# 1-Schematic_GPIO_WAVER.net
KiCad netlist of a schematic drawn in EasyEDA
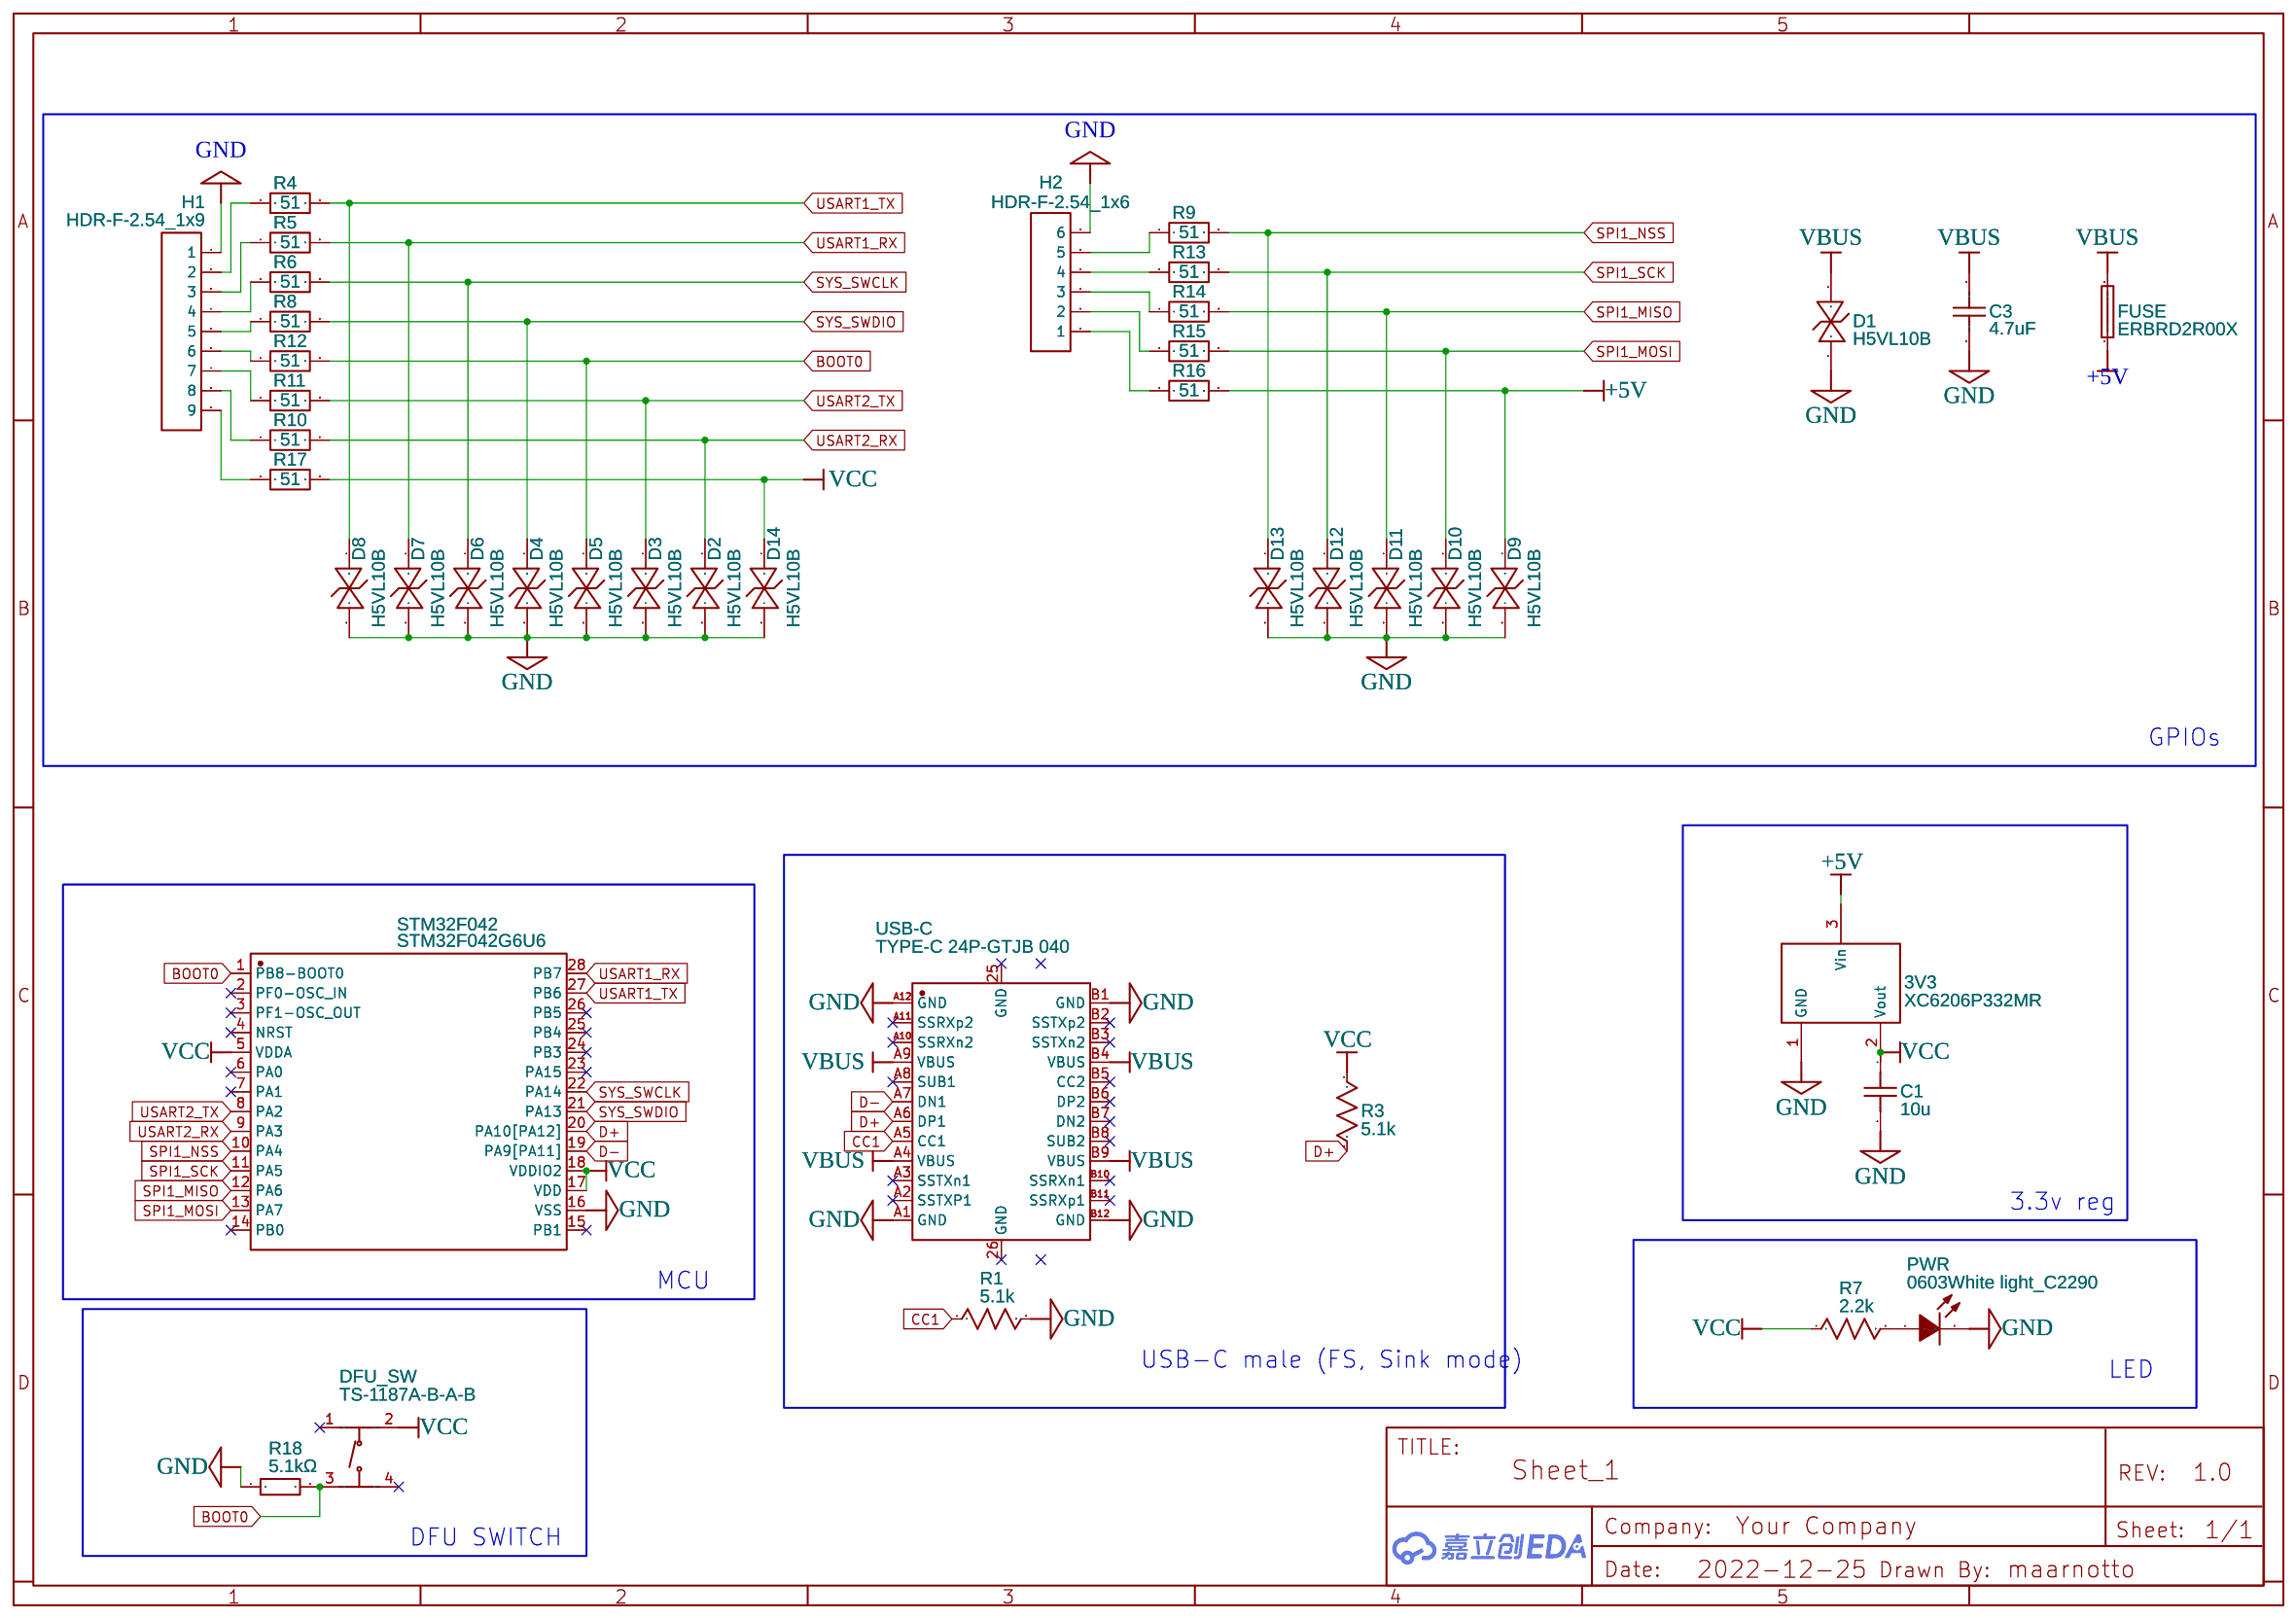
[diagram p0: schematic sheet]

(export (version "E")
  (design (tool "Eeschema 10.0.6"))
  (components
    (comp (ref "3V3")
      (value "XC6206P332MR")
      (fields (field (name "Manufacturer") "TOREX(特瑞仕)"))
      (libsource (lib "") (part "XC6206P332MR"))
    )
    (comp (ref "C1") (value "10u") (libsource (lib "") (part "C_0603_US")))
    (comp (ref "C3") (value "4.7uF") (libsource (lib "") (part "C_0603_US_1")))
    (comp (ref "D1")
      (value "H5VL10B")
      (fields (field (name "Manufacturer") "宏迦橙"))
      (libsource (lib "") (part "H5VL10B"))
    )
    (comp (ref "D2")
      (value "H5VL10B")
      (fields (field (name "Manufacturer") "宏迦橙"))
      (libsource (lib "") (part "H5VL10B"))
    )
    (comp (ref "D3")
      (value "H5VL10B")
      (fields (field (name "Manufacturer") "宏迦橙"))
      (libsource (lib "") (part "H5VL10B"))
    )
    (comp (ref "D4")
      (value "H5VL10B")
      (fields (field (name "Manufacturer") "宏迦橙"))
      (libsource (lib "") (part "H5VL10B"))
    )
    (comp (ref "D5")
      (value "H5VL10B")
      (fields (field (name "Manufacturer") "宏迦橙"))
      (libsource (lib "") (part "H5VL10B"))
    )
    (comp (ref "D6")
      (value "H5VL10B")
      (fields (field (name "Manufacturer") "宏迦橙"))
      (libsource (lib "") (part "H5VL10B"))
    )
    (comp (ref "D7")
      (value "H5VL10B")
      (fields (field (name "Manufacturer") "宏迦橙"))
      (libsource (lib "") (part "H5VL10B"))
    )
    (comp (ref "D8")
      (value "H5VL10B")
      (fields (field (name "Manufacturer") "宏迦橙"))
      (libsource (lib "") (part "H5VL10B"))
    )
    (comp (ref "D9")
      (value "H5VL10B")
      (fields (field (name "Manufacturer") "宏迦橙"))
      (libsource (lib "") (part "H5VL10B"))
    )
    (comp (ref "D10")
      (value "H5VL10B")
      (fields (field (name "Manufacturer") "宏迦橙"))
      (libsource (lib "") (part "H5VL10B"))
    )
    (comp (ref "D11")
      (value "H5VL10B")
      (fields (field (name "Manufacturer") "宏迦橙"))
      (libsource (lib "") (part "H5VL10B"))
    )
    (comp (ref "D12")
      (value "H5VL10B")
      (fields (field (name "Manufacturer") "宏迦橙"))
      (libsource (lib "") (part "H5VL10B"))
    )
    (comp (ref "D13")
      (value "H5VL10B")
      (fields (field (name "Manufacturer") "宏迦橙"))
      (libsource (lib "") (part "H5VL10B"))
    )
    (comp (ref "D14")
      (value "H5VL10B")
      (fields (field (name "Manufacturer") "宏迦橙"))
      (libsource (lib "") (part "H5VL10B"))
    )
    (comp (ref "DFU_SW")
      (value "TS-1187A-B-A-B")
      (fields (field (name "Manufacturer") "XKB Connectivity(中国星坤)"))
      (libsource (lib "") (part "TS-1187A-B-A-B"))
    )
    (comp (ref "FUSE")
      (value "ERBRD2R00X")
      (fields (field (name "Manufacturer") "PANASONIC(松下)"))
      (libsource (lib "") (part "ERBRD2R00X"))
    )
    (comp (ref "H1") (value "HDR-F-2.54_1x9") (libsource (lib "") (part "HDR-F-2.54_1x9")))
    (comp (ref "H2") (value "HDR-F-2.54_1x6") (libsource (lib "") (part "HDR-F-2.54_1x6")))
    (comp (ref "PWR")
      (value "0603White light_C2290")
      (fields (field (name "Manufacturer Part") "KT-0603白灯"))
      (libsource (lib "") (part "0603White light_C2290"))
    )
    (comp (ref "R1") (value "5.1k") (libsource (lib "") (part "R_0603_US")))
    (comp (ref "R3") (value "5.1k") (libsource (lib "") (part "R_0603_US_1")))
    (comp (ref "R4") (value "51") (libsource (lib "") (part "R_0603_EU")))
    (comp (ref "R5") (value "51") (libsource (lib "") (part "R_0603_EU")))
    (comp (ref "R6") (value "51") (libsource (lib "") (part "R_0603_EU")))
    (comp (ref "R7") (value "2.2k") (libsource (lib "") (part "R_0603_US")))
    (comp (ref "R8") (value "51") (libsource (lib "") (part "R_0603_EU")))
    (comp (ref "R9") (value "51") (libsource (lib "") (part "R_0603_EU")))
    (comp (ref "R10") (value "51") (libsource (lib "") (part "R_0603_EU")))
    (comp (ref "R11") (value "51") (libsource (lib "") (part "R_0603_EU")))
    (comp (ref "R12") (value "51") (libsource (lib "") (part "R_0603_EU")))
    (comp (ref "R13") (value "51") (libsource (lib "") (part "R_0603_EU")))
    (comp (ref "R14") (value "51") (libsource (lib "") (part "R_0603_EU")))
    (comp (ref "R15") (value "51") (libsource (lib "") (part "R_0603_EU")))
    (comp (ref "R16") (value "51") (libsource (lib "") (part "R_0603_EU")))
    (comp (ref "R17") (value "51") (libsource (lib "") (part "R_0603_EU")))
    (comp (ref "R18")
      (value "5.1kΩ")
      (fields
        (field (name "Manufacturer Part") "0402WGF5101TCE")
        (field (name "Manufacturer") "UNI-ROYAL(厚声)")
      )
      (libsource (lib "") (part "0402WGF5101TCE"))
    )
    (comp (ref "STM32F042")
      (value "STM32F042G6U6")
      (fields (field (name "Manufacturer") "ST(意法半导体)"))
      (libsource (lib "") (part "STM32F042G6U6"))
    )
    (comp (ref "USB-C")
      (value "TYPE-C 24P-GTJB 040")
      (fields (field (name "Manufacturer") "SHOU HAN(首韩)"))
      (libsource (lib "") (part "TYPE-C 24P-GTJB 040"))
    )
  )
  (nets
    (net (code "1") (name "+5V") (class "Default")
      (node (ref "3V3") (pin "3") (pinfunction "Vin_3") (pintype "unspecified"))
      (node (ref "D9") (pin "1") (pinfunction "C_1") (pintype "unspecified"))
      (node (ref "FUSE") (pin "1") (pinfunction "1_1") (pintype "unspecified"))
      (node (ref "R16") (pin "2") (pinfunction "2_2") (pintype "unspecified"))
    )
    (net (code "2") (name "BOOT0") (class "Default")
      (node (ref "D5") (pin "1") (pinfunction "C_1") (pintype "unspecified"))
      (node (ref "DFU_SW") (pin "3") (pinfunction "C_3") (pintype "unspecified"))
      (node (ref "R12") (pin "2") (pinfunction "2_2") (pintype "unspecified"))
      (node (ref "R18") (pin "2") (pinfunction "2_2") (pintype "input"))
      (node (ref "STM32F042") (pin "1") (pinfunction "PB8-BOOT0_1") (pintype "unspecified"))
    )
    (net (code "3") (name "CC1") (class "Default")
      (node (ref "R1") (pin "1") (pinfunction "1_1") (pintype "unspecified"))
      (node (ref "USB-C") (pin "A5") (pinfunction "CC1_A5") (pintype "unspecified"))
    )
    (net (code "4") (name "D+") (class "Default")
      (node (ref "R3") (pin "2") (pinfunction "2_2") (pintype "unspecified"))
      (node (ref "STM32F042") (pin "20") (pinfunction "PA10[PA12]_20") (pintype "unspecified"))
      (node (ref "USB-C") (pin "A6") (pinfunction "DP1_A6") (pintype "unspecified"))
    )
    (net (code "5") (name "D-") (class "Default")
      (node (ref "STM32F042") (pin "19") (pinfunction "PA9[PA11]_19") (pintype "unspecified"))
      (node (ref "USB-C") (pin "A7") (pinfunction "DN1_A7") (pintype "unspecified"))
    )
    (net (code "6") (name "GND") (class "Default")
      (node (ref "3V3") (pin "1") (pinfunction "GND_1") (pintype "unspecified"))
      (node (ref "C1") (pin "2") (pinfunction "2_2") (pintype "unspecified"))
      (node (ref "C3") (pin "1") (pinfunction "1_1") (pintype "unspecified"))
      (node (ref "D1") (pin "2") (pinfunction "A_2") (pintype "unspecified"))
      (node (ref "D10") (pin "2") (pinfunction "A_2") (pintype "unspecified"))
      (node (ref "D11") (pin "2") (pinfunction "A_2") (pintype "unspecified"))
      (node (ref "D12") (pin "2") (pinfunction "A_2") (pintype "unspecified"))
      (node (ref "D13") (pin "2") (pinfunction "A_2") (pintype "unspecified"))
      (node (ref "D14") (pin "2") (pinfunction "A_2") (pintype "unspecified"))
      (node (ref "D2") (pin "2") (pinfunction "A_2") (pintype "unspecified"))
      (node (ref "D3") (pin "2") (pinfunction "A_2") (pintype "unspecified"))
      (node (ref "D4") (pin "2") (pinfunction "A_2") (pintype "unspecified"))
      (node (ref "D5") (pin "2") (pinfunction "A_2") (pintype "unspecified"))
      (node (ref "D6") (pin "2") (pinfunction "A_2") (pintype "unspecified"))
      (node (ref "D7") (pin "2") (pinfunction "A_2") (pintype "unspecified"))
      (node (ref "D8") (pin "2") (pinfunction "A_2") (pintype "unspecified"))
      (node (ref "D9") (pin "2") (pinfunction "A_2") (pintype "unspecified"))
      (node (ref "H1") (pin "1") (pinfunction "1_1") (pintype "unspecified"))
      (node (ref "H2") (pin "6") (pinfunction "6_6") (pintype "input"))
      (node (ref "PWR") (pin "2") (pinfunction "K_2") (pintype "unspecified"))
      (node (ref "R1") (pin "2") (pinfunction "2_2") (pintype "unspecified"))
      (node (ref "R18") (pin "1") (pinfunction "1_1") (pintype "input"))
      (node (ref "STM32F042") (pin "16") (pinfunction "VSS_16") (pintype "unspecified"))
      (node (ref "USB-C") (pin "A1") (pinfunction "GND_A1") (pintype "unspecified"))
      (node (ref "USB-C") (pin "A12") (pinfunction "GND_A12") (pintype "unspecified"))
      (node (ref "USB-C") (pin "B1") (pinfunction "GND_B1") (pintype "unspecified"))
      (node (ref "USB-C") (pin "B12") (pinfunction "GND_B12") (pintype "unspecified"))
    )
    (net (code "7") (name "Net-(H1-Pad2)") (class "Default")
      (node (ref "H1") (pin "2") (pinfunction "2_2") (pintype "unspecified"))
      (node (ref "R4") (pin "1") (pinfunction "1_1") (pintype "unspecified"))
    )
    (net (code "8") (name "Net-(H1-Pad3)") (class "Default")
      (node (ref "H1") (pin "3") (pinfunction "3_3") (pintype "unspecified"))
      (node (ref "R5") (pin "1") (pinfunction "1_1") (pintype "unspecified"))
    )
    (net (code "9") (name "Net-(H1-Pad4)") (class "Default")
      (node (ref "H1") (pin "4") (pinfunction "4_4") (pintype "unspecified"))
      (node (ref "R6") (pin "1") (pinfunction "1_1") (pintype "unspecified"))
    )
    (net (code "10") (name "Net-(H1-Pad5)") (class "Default")
      (node (ref "H1") (pin "5") (pinfunction "5_5") (pintype "unspecified"))
      (node (ref "R8") (pin "1") (pinfunction "1_1") (pintype "unspecified"))
    )
    (net (code "11") (name "Net-(H1-Pad6)") (class "Default")
      (node (ref "H1") (pin "6") (pinfunction "6_6") (pintype "unspecified"))
      (node (ref "R12") (pin "1") (pinfunction "1_1") (pintype "unspecified"))
    )
    (net (code "12") (name "Net-(H1-Pad7)") (class "Default")
      (node (ref "H1") (pin "7") (pinfunction "7_7") (pintype "unspecified"))
      (node (ref "R11") (pin "1") (pinfunction "1_1") (pintype "unspecified"))
    )
    (net (code "13") (name "Net-(H1-Pad8)") (class "Default")
      (node (ref "H1") (pin "8") (pinfunction "8_8") (pintype "unspecified"))
      (node (ref "R10") (pin "1") (pinfunction "1_1") (pintype "unspecified"))
    )
    (net (code "14") (name "Net-(H1-Pad9)") (class "Default")
      (node (ref "H1") (pin "9") (pinfunction "9_9") (pintype "unspecified"))
      (node (ref "R17") (pin "1") (pinfunction "1_1") (pintype "unspecified"))
    )
    (net (code "15") (name "Net-(H2-Pad1)") (class "Default")
      (node (ref "H2") (pin "1") (pinfunction "1_1") (pintype "input"))
      (node (ref "R16") (pin "1") (pinfunction "1_1") (pintype "unspecified"))
    )
    (net (code "16") (name "Net-(H2-Pad2)") (class "Default")
      (node (ref "H2") (pin "2") (pinfunction "2_2") (pintype "input"))
      (node (ref "R15") (pin "1") (pinfunction "1_1") (pintype "unspecified"))
    )
    (net (code "17") (name "Net-(H2-Pad3)") (class "Default")
      (node (ref "H2") (pin "3") (pinfunction "3_3") (pintype "input"))
      (node (ref "R14") (pin "1") (pinfunction "1_1") (pintype "unspecified"))
    )
    (net (code "18") (name "Net-(H2-Pad4)") (class "Default")
      (node (ref "H2") (pin "4") (pinfunction "4_4") (pintype "input"))
      (node (ref "R13") (pin "1") (pinfunction "1_1") (pintype "unspecified"))
    )
    (net (code "19") (name "Net-(H2-Pad5)") (class "Default")
      (node (ref "H2") (pin "5") (pinfunction "5_5") (pintype "input"))
      (node (ref "R9") (pin "1") (pinfunction "1_1") (pintype "unspecified"))
    )
    (net (code "20") (name "Net-(PWR-A)") (class "Default")
      (node (ref "PWR") (pin "1") (pinfunction "A_1") (pintype "unspecified"))
      (node (ref "R7") (pin "2") (pinfunction "2_2") (pintype "unspecified"))
    )
    (net (code "21") (name "SPI1_MISO") (class "Default")
      (node (ref "D11") (pin "1") (pinfunction "C_1") (pintype "unspecified"))
      (node (ref "R14") (pin "2") (pinfunction "2_2") (pintype "unspecified"))
      (node (ref "STM32F042") (pin "12") (pinfunction "PA6_12") (pintype "unspecified"))
    )
    (net (code "22") (name "SPI1_MOSI") (class "Default")
      (node (ref "D10") (pin "1") (pinfunction "C_1") (pintype "unspecified"))
      (node (ref "R15") (pin "2") (pinfunction "2_2") (pintype "unspecified"))
      (node (ref "STM32F042") (pin "13") (pinfunction "PA7_13") (pintype "unspecified"))
    )
    (net (code "23") (name "SPI1_NSS") (class "Default")
      (node (ref "D13") (pin "1") (pinfunction "C_1") (pintype "unspecified"))
      (node (ref "R9") (pin "2") (pinfunction "2_2") (pintype "unspecified"))
      (node (ref "STM32F042") (pin "10") (pinfunction "PA4_10") (pintype "unspecified"))
    )
    (net (code "24") (name "SPI1_SCK") (class "Default")
      (node (ref "D12") (pin "1") (pinfunction "C_1") (pintype "unspecified"))
      (node (ref "R13") (pin "2") (pinfunction "2_2") (pintype "unspecified"))
      (node (ref "STM32F042") (pin "11") (pinfunction "PA5_11") (pintype "unspecified"))
    )
    (net (code "25") (name "SYS_SWCLK") (class "Default")
      (node (ref "D6") (pin "1") (pinfunction "C_1") (pintype "unspecified"))
      (node (ref "R6") (pin "2") (pinfunction "2_2") (pintype "unspecified"))
      (node (ref "STM32F042") (pin "22") (pinfunction "PA14_22") (pintype "unspecified"))
    )
    (net (code "26") (name "SYS_SWDIO") (class "Default")
      (node (ref "D4") (pin "1") (pinfunction "C_1") (pintype "unspecified"))
      (node (ref "R8") (pin "2") (pinfunction "2_2") (pintype "unspecified"))
      (node (ref "STM32F042") (pin "21") (pinfunction "PA13_21") (pintype "unspecified"))
    )
    (net (code "27") (name "USART1_RX") (class "Default")
      (node (ref "D7") (pin "1") (pinfunction "C_1") (pintype "unspecified"))
      (node (ref "R5") (pin "2") (pinfunction "2_2") (pintype "unspecified"))
      (node (ref "STM32F042") (pin "28") (pinfunction "PB7_28") (pintype "unspecified"))
    )
    (net (code "28") (name "USART1_TX") (class "Default")
      (node (ref "D8") (pin "1") (pinfunction "C_1") (pintype "unspecified"))
      (node (ref "R4") (pin "2") (pinfunction "2_2") (pintype "unspecified"))
      (node (ref "STM32F042") (pin "27") (pinfunction "PB6_27") (pintype "unspecified"))
    )
    (net (code "29") (name "USART2_RX") (class "Default")
      (node (ref "D2") (pin "1") (pinfunction "C_1") (pintype "unspecified"))
      (node (ref "R10") (pin "2") (pinfunction "2_2") (pintype "unspecified"))
      (node (ref "STM32F042") (pin "9") (pinfunction "PA3_9") (pintype "unspecified"))
    )
    (net (code "30") (name "USART2_TX") (class "Default")
      (node (ref "D3") (pin "1") (pinfunction "C_1") (pintype "unspecified"))
      (node (ref "R11") (pin "2") (pinfunction "2_2") (pintype "unspecified"))
      (node (ref "STM32F042") (pin "8") (pinfunction "PA2_8") (pintype "unspecified"))
    )
    (net (code "31") (name "VBUS") (class "Default")
      (node (ref "C3") (pin "2") (pinfunction "2_2") (pintype "unspecified"))
      (node (ref "D1") (pin "1") (pinfunction "C_1") (pintype "unspecified"))
      (node (ref "FUSE") (pin "2") (pinfunction "2_2") (pintype "unspecified"))
      (node (ref "USB-C") (pin "A4") (pinfunction "VBUS_A4") (pintype "unspecified"))
      (node (ref "USB-C") (pin "A9") (pinfunction "VBUS_A9") (pintype "unspecified"))
      (node (ref "USB-C") (pin "B4") (pinfunction "VBUS_B4") (pintype "unspecified"))
      (node (ref "USB-C") (pin "B9") (pinfunction "VBUS_B9") (pintype "unspecified"))
    )
    (net (code "32") (name "VCC") (class "Default")
      (node (ref "3V3") (pin "2") (pinfunction "Vout_2") (pintype "unspecified"))
      (node (ref "C1") (pin "1") (pinfunction "1_1") (pintype "unspecified"))
      (node (ref "D14") (pin "1") (pinfunction "C_1") (pintype "unspecified"))
      (node (ref "DFU_SW") (pin "2") (pinfunction "B_2") (pintype "unspecified"))
      (node (ref "R17") (pin "2") (pinfunction "2_2") (pintype "unspecified"))
      (node (ref "R3") (pin "1") (pinfunction "1_1") (pintype "unspecified"))
      (node (ref "R7") (pin "1") (pinfunction "1_1") (pintype "unspecified"))
      (node (ref "STM32F042") (pin "17") (pinfunction "VDD_17") (pintype "unspecified"))
      (node (ref "STM32F042") (pin "18") (pinfunction "VDDIO2_18") (pintype "unspecified"))
      (node (ref "STM32F042") (pin "5") (pinfunction "VDDA_5") (pintype "unspecified"))
    )
    (net (code "33") (name "unconnected-(DFU_SW-A-Pad1)") (class "Default")
      (node (ref "DFU_SW") (pin "1") (pinfunction "A_1") (pintype "unspecified+no_connect"))
    )
    (net (code "34") (name "unconnected-(DFU_SW-D-Pad4)") (class "Default")
      (node (ref "DFU_SW") (pin "4") (pinfunction "D_4") (pintype "unspecified+no_connect"))
    )
    (net (code "35") (name "unconnected-(STM32F042-NRST-Pad4)") (class "Default")
      (node (ref "STM32F042") (pin "4") (pinfunction "NRST_4") (pintype "unspecified+no_connect"))
    )
    (net (code "36") (name "unconnected-(STM32F042-PA0-Pad6)") (class "Default")
      (node (ref "STM32F042") (pin "6") (pinfunction "PA0_6") (pintype "unspecified+no_connect"))
    )
    (net (code "37") (name "unconnected-(STM32F042-PA1-Pad7)") (class "Default")
      (node (ref "STM32F042") (pin "7") (pinfunction "PA1_7") (pintype "unspecified+no_connect"))
    )
    (net (code "38") (name "unconnected-(STM32F042-PA15-Pad23)") (class "Default")
      (node (ref "STM32F042") (pin "23") (pinfunction "PA15_23") (pintype "unspecified+no_connect"))
    )
    (net (code "39") (name "unconnected-(STM32F042-PB0-Pad14)") (class "Default")
      (node (ref "STM32F042") (pin "14") (pinfunction "PB0_14") (pintype "unspecified+no_connect"))
    )
    (net (code "40") (name "unconnected-(STM32F042-PB1-Pad15)") (class "Default")
      (node (ref "STM32F042") (pin "15") (pinfunction "PB1_15") (pintype "unspecified+no_connect"))
    )
    (net (code "41") (name "unconnected-(STM32F042-PB3-Pad24)") (class "Default")
      (node (ref "STM32F042") (pin "24") (pinfunction "PB3_24") (pintype "unspecified+no_connect"))
    )
    (net (code "42") (name "unconnected-(STM32F042-PB4-Pad25)") (class "Default")
      (node (ref "STM32F042") (pin "25") (pinfunction "PB4_25") (pintype "unspecified+no_connect"))
    )
    (net (code "43") (name "unconnected-(STM32F042-PB5-Pad26)") (class "Default")
      (node (ref "STM32F042") (pin "26") (pinfunction "PB5_26") (pintype "unspecified+no_connect"))
    )
    (net (code "44") (name "unconnected-(STM32F042-PF0-OSC_IN-Pad2)") (class "Default")
      (node (ref "STM32F042") (pin "2") (pinfunction "PF0-OSC_IN_2") (pintype "unspecified+no_connect"))
    )
    (net (code "45") (name "unconnected-(STM32F042-PF1-OSC_OUT-Pad3)") (class "Default")
      (node (ref "STM32F042") (pin "3") (pinfunction "PF1-OSC_OUT_3") (pintype "unspecified+no_connect"))
    )
    (net (code "46") (name "unconnected-(USB-C-CC2-PadB5)") (class "Default")
      (node (ref "USB-C") (pin "B5") (pinfunction "CC2_B5") (pintype "unspecified+no_connect"))
    )
    (net (code "47") (name "unconnected-(USB-C-DN2-PadB7)") (class "Default")
      (node (ref "USB-C") (pin "B7") (pinfunction "DN2_B7") (pintype "unspecified+no_connect"))
    )
    (net (code "48") (name "unconnected-(USB-C-DP2-PadB6)") (class "Default")
      (node (ref "USB-C") (pin "B6") (pinfunction "DP2_B6") (pintype "unspecified+no_connect"))
    )
    (net (code "49") (name "unconnected-(USB-C-GND-Pad25)") (class "Default")
      (node (ref "USB-C") (pin "25") (pinfunction "GND_25") (pintype "unspecified+no_connect"))
    )
    (net (code "50") (name "unconnected-(USB-C-GND-Pad26)") (class "Default")
      (node (ref "USB-C") (pin "26") (pinfunction "GND_26") (pintype "unspecified+no_connect"))
    )
    (net (code "51") (name "unconnected-(USB-C-SSRXn1-PadB10)") (class "Default")
      (node (ref "USB-C") (pin "B10") (pinfunction "SSRXn1_B10") (pintype "unspecified+no_connect"))
    )
    (net (code "52") (name "unconnected-(USB-C-SSRXn2-PadA10)") (class "Default")
      (node (ref "USB-C") (pin "A10") (pinfunction "SSRXn2_A10") (pintype "unspecified+no_connect"))
    )
    (net (code "53") (name "unconnected-(USB-C-SSRXp1-PadB11)") (class "Default")
      (node (ref "USB-C") (pin "B11") (pinfunction "SSRXp1_B11") (pintype "unspecified+no_connect"))
    )
    (net (code "54") (name "unconnected-(USB-C-SSRXp2-PadA11)") (class "Default")
      (node (ref "USB-C") (pin "A11") (pinfunction "SSRXp2_A11") (pintype "unspecified+no_connect"))
    )
    (net (code "55") (name "unconnected-(USB-C-SSTXP1-PadA2)") (class "Default")
      (node (ref "USB-C") (pin "A2") (pinfunction "SSTXP1_A2") (pintype "unspecified+no_connect"))
    )
    (net (code "56") (name "unconnected-(USB-C-SSTXn1-PadA3)") (class "Default")
      (node (ref "USB-C") (pin "A3") (pinfunction "SSTXn1_A3") (pintype "unspecified+no_connect"))
    )
    (net (code "57") (name "unconnected-(USB-C-SSTXn2-PadB3)") (class "Default")
      (node (ref "USB-C") (pin "B3") (pinfunction "SSTXn2_B3") (pintype "unspecified+no_connect"))
    )
    (net (code "58") (name "unconnected-(USB-C-SSTXp2-PadB2)") (class "Default")
      (node (ref "USB-C") (pin "B2") (pinfunction "SSTXp2_B2") (pintype "unspecified+no_connect"))
    )
    (net (code "59") (name "unconnected-(USB-C-SUB1-PadA8)") (class "Default")
      (node (ref "USB-C") (pin "A8") (pinfunction "SUB1_A8") (pintype "unspecified+no_connect"))
    )
    (net (code "60") (name "unconnected-(USB-C-SUB2-PadB8)") (class "Default")
      (node (ref "USB-C") (pin "B8") (pinfunction "SUB2_B8") (pintype "unspecified+no_connect"))
    )
  )
)
